# MTRduino_Rev3_1.net
KiCad netlist of a schematic drawn in EAGLE
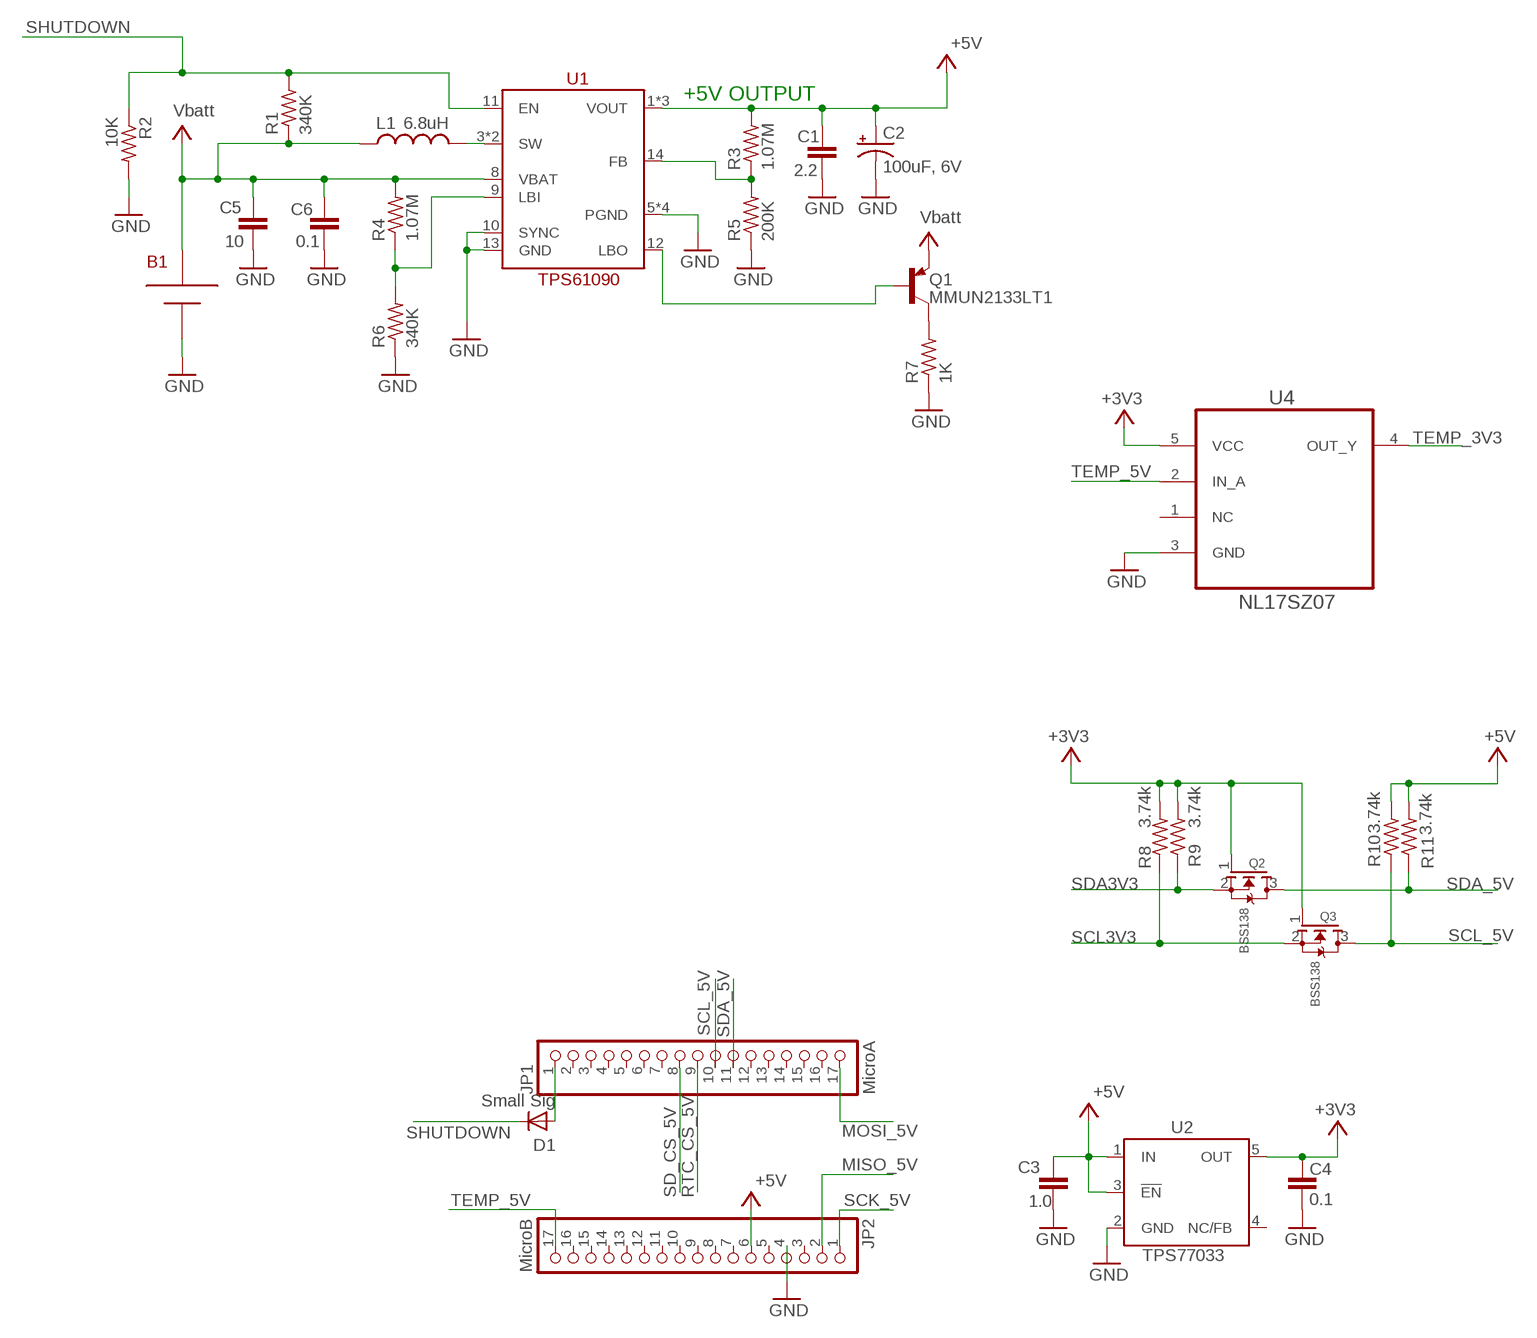
[diagram p0: schematic, sheet 1, part 1 of 2]
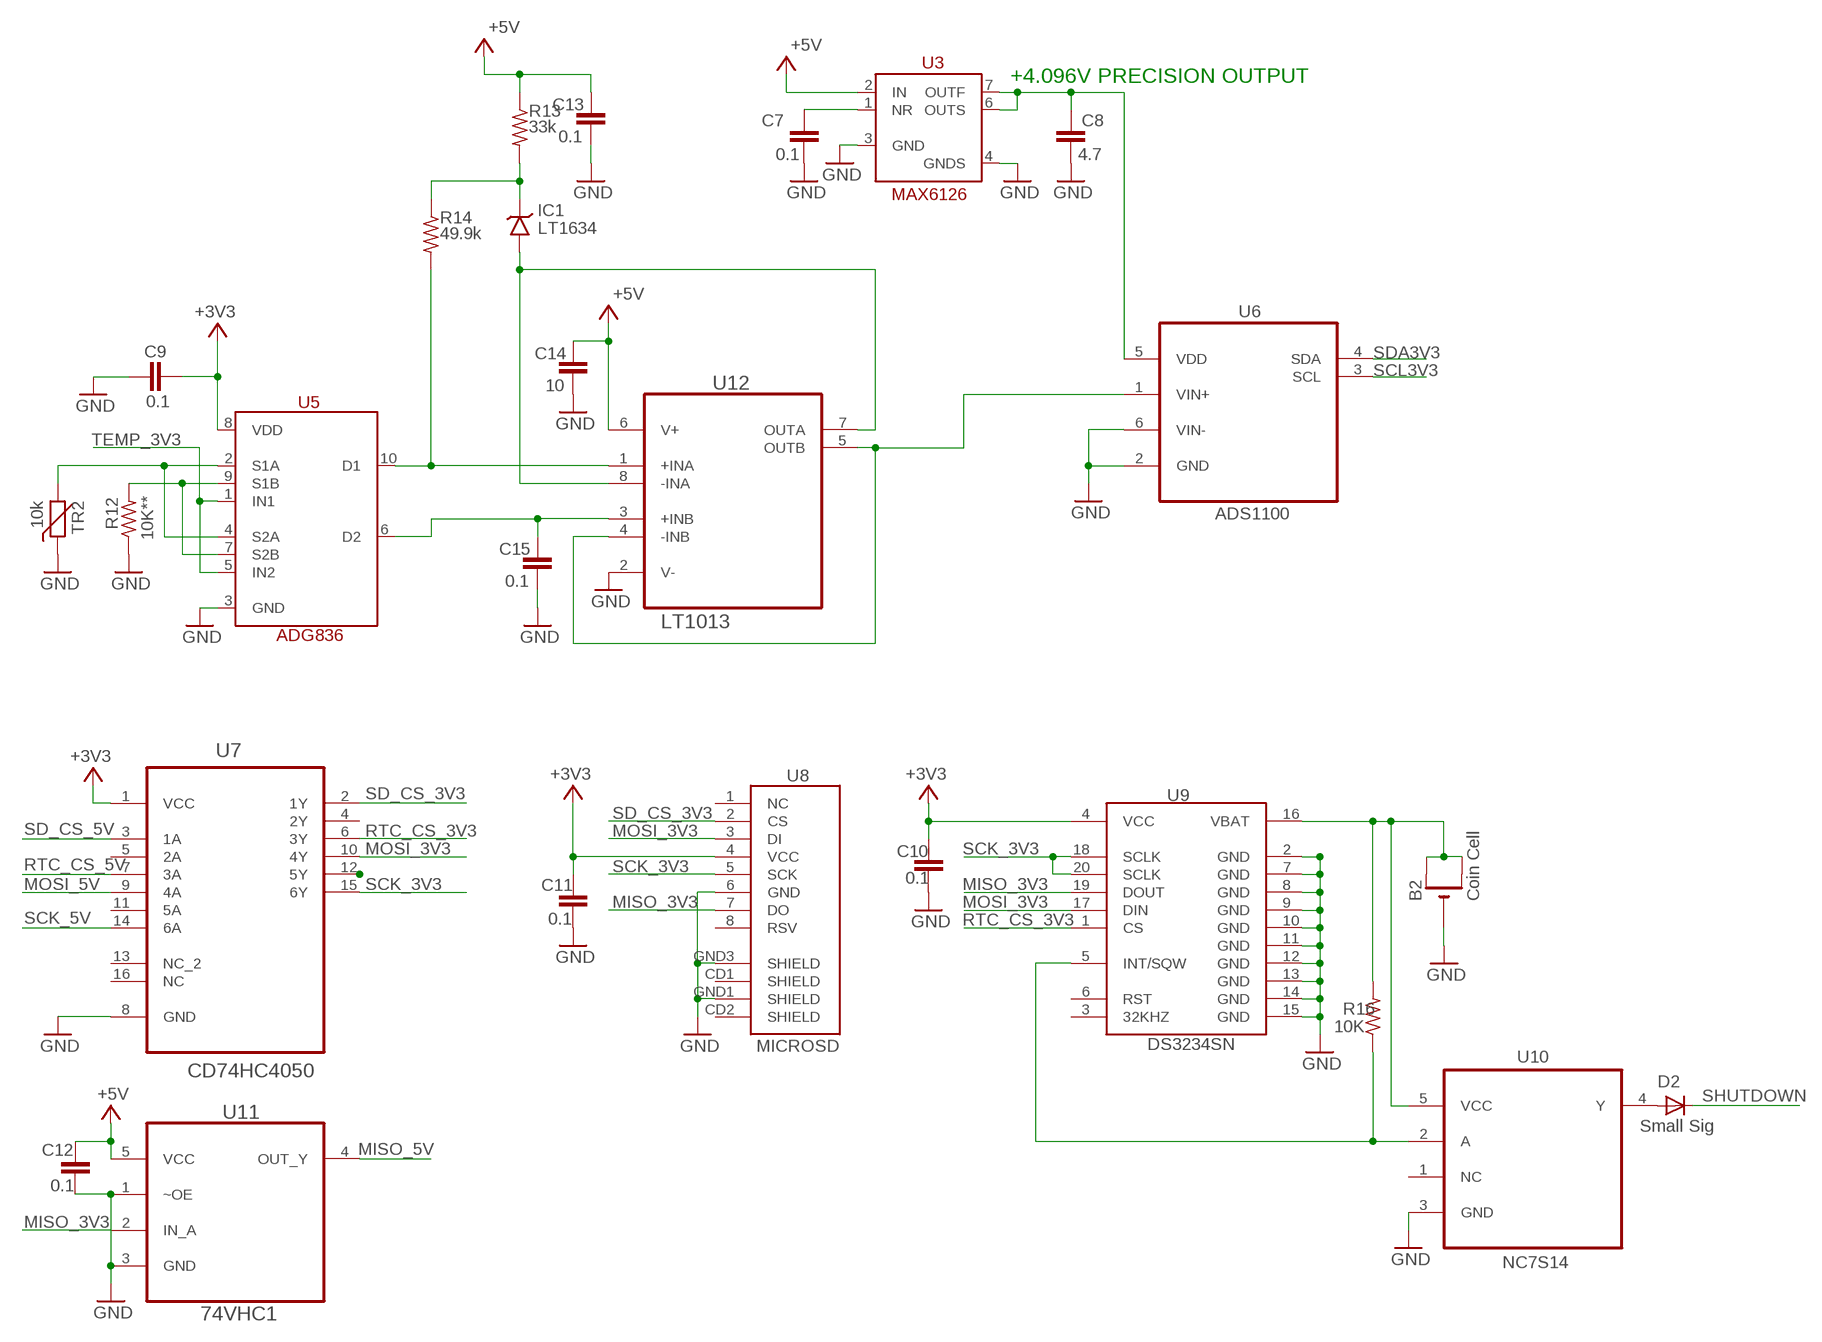
[diagram p1: schematic, sheet 1, part 2 of 2]

(export (version "E")
  (design (tool "Eeschema 10.0.6"))
  (components
    (comp (ref "B1")
      (value "2x AA BATT")
      (footprint "eagle-import:BATT_AA2")
      (libsource (lib "eagle-import") (part "BATT_AA2"))
    )
    (comp (ref "B2")
      (value "Coin Cell")
      (footprint "eagle-import:CR1220-SMD")
      (libsource (lib "eagle-import") (part "CR1220SMT"))
    )
    (comp (ref "C1")
      (value "2.2")
      (footprint "eagle-import:C0603")
      (libsource (lib "eagle-import") (part "C-EUC0603"))
    )
    (comp (ref "C2")
      (value "100uF, 6V")
      (footprint "eagle-import:A_3216-18R")
      (libsource (lib "eagle-import") (part "CPOL-USA/3216-18R"))
    )
    (comp (ref "C3")
      (value "1.0")
      (footprint "eagle-import:C0603")
      (libsource (lib "eagle-import") (part "C-EUC0603"))
    )
    (comp (ref "C4")
      (value "0.1")
      (footprint "eagle-import:C0603")
      (libsource (lib "eagle-import") (part "C-EUC0603"))
    )
    (comp (ref "C5")
      (value "10")
      (footprint "eagle-import:C0603")
      (libsource (lib "eagle-import") (part "C-EUC0603"))
    )
    (comp (ref "C6")
      (value "0.1")
      (footprint "eagle-import:C0603")
      (libsource (lib "eagle-import") (part "C-EUC0603"))
    )
    (comp (ref "C7")
      (value "0.1")
      (footprint "eagle-import:C0603")
      (libsource (lib "eagle-import") (part "C-EUC0603"))
    )
    (comp (ref "C8")
      (value "4.7")
      (footprint "eagle-import:C0603")
      (libsource (lib "eagle-import") (part "C-EUC0603"))
    )
    (comp (ref "C9")
      (value "0.1")
      (footprint "eagle-import:C0603")
      (libsource (lib "eagle-import") (part "C-EUC0603"))
    )
    (comp (ref "C10")
      (value "0.1")
      (footprint "eagle-import:C0603")
      (libsource (lib "eagle-import") (part "C-EUC0603"))
    )
    (comp (ref "C11")
      (value "0.1")
      (footprint "eagle-import:C0603")
      (libsource (lib "eagle-import") (part "C-EUC0603"))
    )
    (comp (ref "C12")
      (value "0.1")
      (footprint "eagle-import:C0603")
      (libsource (lib "eagle-import") (part "C-EUC0603"))
    )
    (comp (ref "C13")
      (value "0.1")
      (footprint "eagle-import:C0603")
      (libsource (lib "eagle-import") (part "C-EUC0603"))
    )
    (comp (ref "C14")
      (value "10")
      (footprint "eagle-import:C0603")
      (libsource (lib "eagle-import") (part "C-EUC0603"))
    )
    (comp (ref "C15")
      (value "0.1")
      (footprint "eagle-import:C0603")
      (libsource (lib "eagle-import") (part "C-EUC0603"))
    )
    (comp (ref "D1")
      (value "Small Sig")
      (footprint "eagle-import:SOD-323F")
      (libsource (lib "eagle-import") (part "DIODESOD-323F"))
    )
    (comp (ref "D2")
      (value "Small Sig")
      (footprint "eagle-import:SOD-323F")
      (libsource (lib "eagle-import") (part "DIODESOD-323F"))
    )
    (comp (ref "IC1")
      (value "LT1634")
      (footprint "eagle-import:S8")
      (libsource (lib "eagle-import") (part "LT1634BIS8-1.25"))
    )
    (comp (ref "JP1")
      (value "MicroA")
      (footprint "eagle-import:1X17")
      (libsource (lib "eagle-import") (part "PINHD-1X17"))
    )
    (comp (ref "JP2")
      (value "MicroB")
      (footprint "eagle-import:1X17")
      (libsource (lib "eagle-import") (part "PINHD-1X17"))
    )
    (comp (ref "L1")
      (value "6.8uH")
      (footprint "eagle-import:L2012C")
      (libsource (lib "eagle-import") (part "L-USL2012C"))
    )
    (comp (ref "Q1")
      (value "MMUN2133LT1")
      (footprint "eagle-import:SC59-BEC")
      (libsource (lib "eagle-import") (part "MMUN2111LT1"))
    )
    (comp (ref "Q2")
      (value "BSS138")
      (footprint "eagle-import:SOT23")
      (libsource (lib "eagle-import") (part "MOSFET-NREFLOW"))
    )
    (comp (ref "Q3")
      (value "BSS138")
      (footprint "eagle-import:SOT23")
      (libsource (lib "eagle-import") (part "MOSFET-NREFLOW"))
    )
    (comp (ref "R1")
      (value "340K")
      (footprint "eagle-import:R0603")
      (libsource (lib "eagle-import") (part "resistor_R-US_R0603"))
    )
    (comp (ref "R2")
      (value "10K")
      (footprint "eagle-import:R0603")
      (libsource (lib "eagle-import") (part "resistor_R-US_R0603"))
    )
    (comp (ref "R3")
      (value "1.07M")
      (footprint "eagle-import:R0603")
      (libsource (lib "eagle-import") (part "resistor_R-US_R0603"))
    )
    (comp (ref "R4")
      (value "1.07M")
      (footprint "eagle-import:R0603")
      (libsource (lib "eagle-import") (part "resistor_R-US_R0603"))
    )
    (comp (ref "R5")
      (value "200K")
      (footprint "eagle-import:R0603")
      (libsource (lib "eagle-import") (part "resistor_R-US_R0603"))
    )
    (comp (ref "R6")
      (value "340K")
      (footprint "eagle-import:R0603")
      (libsource (lib "eagle-import") (part "resistor_R-US_R0603"))
    )
    (comp (ref "R7")
      (value "1K")
      (footprint "eagle-import:R0603")
      (libsource (lib "eagle-import") (part "resistor_R-US_R0603"))
    )
    (comp (ref "R8")
      (value "3.74k")
      (footprint "eagle-import:R0603")
      (libsource (lib "eagle-import") (part "resistor_R-US_R0603"))
    )
    (comp (ref "R9")
      (value "3.74k")
      (footprint "eagle-import:R0603")
      (libsource (lib "eagle-import") (part "resistor_R-US_R0603"))
    )
    (comp (ref "R10")
      (value "3.74k")
      (footprint "eagle-import:R0603")
      (libsource (lib "eagle-import") (part "resistor_R-US_R0603"))
    )
    (comp (ref "R11")
      (value "3.74k")
      (footprint "eagle-import:R0603")
      (libsource (lib "eagle-import") (part "resistor_R-US_R0603"))
    )
    (comp (ref "R12")
      (value "10K**")
      (footprint "eagle-import:R1206")
      (libsource (lib "eagle-import") (part "R-US_R1206"))
    )
    (comp (ref "R13")
      (value "33k")
      (footprint "eagle-import:R0603")
      (libsource (lib "eagle-import") (part "resistor_R-US_R0603"))
    )
    (comp (ref "R14")
      (value "49.9k")
      (footprint "eagle-import:R0603")
      (libsource (lib "eagle-import") (part "resistor_R-US_R0603"))
    )
    (comp (ref "R16")
      (value "10K")
      (footprint "eagle-import:R0603")
      (libsource (lib "eagle-import") (part "resistor_R-US_R0603"))
    )
    (comp (ref "TR2")
      (value "10k")
      (footprint "eagle-import:R-5")
      (libsource (lib "eagle-import") (part "THERMISTOR_R-5"))
    )
    (comp (ref "U1")
      (value "TPS61090")
      (footprint "eagle-import:QFN16-4X4")
      (libsource (lib "eagle-import") (part "TPS61090RSAR"))
    )
    (comp (ref "U2")
      (value "TPS77033")
      (footprint "eagle-import:SOT23-DBV")
      (fields (field (name "MF") "TEXAS INSTRUMENTS") (field (name "MPN") "TPS77030DBVT"))
      (libsource (lib "eagle-import") (part "TPS77030"))
    )
    (comp (ref "U3")
      (value "MAX6126")
      (footprint "eagle-import:SOIC127P600X175-8N")
      (libsource (lib "eagle-import") (part "MAX6126"))
    )
    (comp (ref "U4")
      (value "NL17SZ07")
      (footprint "eagle-import:SOT65P210X110-5N")
      (fields (field (name "MPN") "NL17SZ07DFT2G"))
      (libsource (lib "eagle-import") (part "NL17SZ07DFT2G"))
    )
    (comp (ref "U5")
      (value "ADG836")
      (footprint "eagle-import:MSOP10")
      (libsource (lib "eagle-import") (part "ADG836"))
    )
    (comp (ref "U6")
      (value "ADS1100")
      (footprint "eagle-import:SOT95P280X145-6N")
      (fields (field (name "MPN") "ADS1100A0IDBVT"))
      (libsource (lib "eagle-import") (part "ADS1100A0IDBVT"))
    )
    (comp (ref "U7")
      (value "CD74HC4050")
      (footprint "eagle-import:SOIC127P600X175-16N")
      (fields (field (name "MPN") "M74HC4050RM13TR"))
      (libsource (lib "eagle-import") (part "M74HC4050RM13TR"))
    )
    (comp (ref "U8")
      (value "MICROSD")
      (footprint "eagle-import:MICRO-SD-SOCKET-PP")
      (libsource (lib "eagle-import") (part "USD-SOCKETNEW"))
    )
    (comp (ref "U9")
      (value "DS3234SN")
      (footprint "eagle-import:DS3234")
      (libsource (lib "eagle-import") (part "DS3234"))
    )
    (comp (ref "U10")
      (value "NC7S14")
      (footprint "eagle-import:SOT95P280X145-5N")
      (fields (field (name "MPN") "1P1G14MDBVREPG4"))
      (libsource (lib "eagle-import") (part "1P1G14MDBVREPG4"))
    )
    (comp (ref "U11")
      (value "74VHC1")
      (footprint "eagle-import:SOT65P210X110-5N")
      (fields (field (name "MPN") "M74VHC1GT125DF1G"))
      (libsource (lib "eagle-import") (part "M74VHC1GT125DF1G"))
    )
    (comp (ref "U12")
      (value "LT1013")
      (footprint "eagle-import:SOIC127P600X175-8N")
      (fields (field (name "MPN") "LT1013DS8#PBF"))
      (libsource (lib "eagle-import") (part "LT1013DS8PBF"))
    )
  )
  (nets
    (net (code "1") (name "+3V3") (class "Default")
      (node (ref "C10") (pin "1") (pinfunction "1_1") (pintype "passive"))
      (node (ref "C11") (pin "1") (pinfunction "1_1") (pintype "passive"))
      (node (ref "C4") (pin "1") (pinfunction "1_1") (pintype "passive"))
      (node (ref "C9") (pin "2") (pinfunction "2_2") (pintype "passive"))
      (node (ref "Q2") (pin "1") (pinfunction "G_1") (pintype "bidirectional"))
      (node (ref "Q3") (pin "1") (pinfunction "G_1") (pintype "bidirectional"))
      (node (ref "R8") (pin "2") (pinfunction "2_2") (pintype "passive"))
      (node (ref "R9") (pin "2") (pinfunction "2_2") (pintype "passive"))
      (node (ref "U2") (pin "5") (pinfunction "OUT_5") (pintype "passive"))
      (node (ref "U4") (pin "5") (pinfunction "VCC_5") (pintype "power_in"))
      (node (ref "U5") (pin "8") (pinfunction "VDD_8") (pintype "bidirectional"))
      (node (ref "U7") (pin "1") (pinfunction "VCC_1") (pintype "power_in"))
      (node (ref "U8") (pin "4") (pinfunction "VCC_4") (pintype "bidirectional"))
      (node (ref "U9") (pin "4") (pinfunction "VCC_4") (pintype "bidirectional"))
    )
    (net (code "2") (name "+5V") (class "Default")
      (node (ref "C1") (pin "1") (pinfunction "1_1") (pintype "passive"))
      (node (ref "C12") (pin "1") (pinfunction "1_1") (pintype "passive"))
      (node (ref "C13") (pin "2") (pinfunction "2_2") (pintype "passive"))
      (node (ref "C14") (pin "2") (pinfunction "2_2") (pintype "passive"))
      (node (ref "C2") (pin "+") (pinfunction "+_+") (pintype "passive"))
      (node (ref "C3") (pin "1") (pinfunction "1_1") (pintype "passive"))
      (node (ref "JP2") (pin "6") (pinfunction "6_6") (pintype "passive"))
      (node (ref "R10") (pin "2") (pinfunction "2_2") (pintype "passive"))
      (node (ref "R11") (pin "2") (pinfunction "2_2") (pintype "passive"))
      (node (ref "R13") (pin "1") (pinfunction "1_1") (pintype "passive"))
      (node (ref "R3") (pin "2") (pinfunction "2_2") (pintype "passive"))
      (node (ref "U1") (pin "1") (pinfunction "VOUT_1") (pintype "bidirectional"))
      (node (ref "U1") (pin "15") (pinfunction "VOUT_15") (pintype "bidirectional"))
      (node (ref "U1") (pin "16") (pinfunction "VOUT_16") (pintype "bidirectional"))
      (node (ref "U11") (pin "5") (pinfunction "VCC_5") (pintype "power_in"))
      (node (ref "U12") (pin "6") (pinfunction "V+_6") (pintype "power_in"))
      (node (ref "U2") (pin "1") (pinfunction "IN_1") (pintype "input"))
      (node (ref "U2") (pin "3") (pinfunction "~{EN}_3") (pintype "input"))
      (node (ref "U3") (pin "2") (pinfunction "IN_2") (pintype "input"))
    )
    (net (code "3") (name "/MISO_3V3") (class "Default")
      (node (ref "U11") (pin "2") (pinfunction "IN_A_2") (pintype "input"))
      (node (ref "U8") (pin "7") (pinfunction "DO_7") (pintype "bidirectional"))
      (node (ref "U9") (pin "19") (pinfunction "DOUT_19") (pintype "bidirectional"))
    )
    (net (code "4") (name "/MISO_5V") (class "Default")
      (node (ref "JP2") (pin "2") (pinfunction "2_2") (pintype "passive"))
      (node (ref "U11") (pin "4") (pinfunction "OUT_Y_4") (pintype "output"))
    )
    (net (code "5") (name "/MOSI_3V3") (class "Default")
      (node (ref "U7") (pin "10") (pinfunction "4Y_10") (pintype "output"))
      (node (ref "U8") (pin "3") (pinfunction "DI_3") (pintype "bidirectional"))
      (node (ref "U9") (pin "17") (pinfunction "DIN_17") (pintype "bidirectional"))
    )
    (net (code "6") (name "/MOSI_5V") (class "Default")
      (node (ref "JP1") (pin "17") (pinfunction "17_17") (pintype "passive"))
      (node (ref "U7") (pin "9") (pinfunction "4A_9") (pintype "input"))
    )
    (net (code "7") (name "/RTC_CS_3V3") (class "Default")
      (node (ref "U7") (pin "6") (pinfunction "3Y_6") (pintype "output"))
      (node (ref "U9") (pin "1") (pinfunction "CS_1") (pintype "bidirectional"))
    )
    (net (code "8") (name "/RTC_CS_5V") (class "Default")
      (node (ref "JP1") (pin "9") (pinfunction "9_9") (pintype "passive"))
      (node (ref "U7") (pin "7") (pinfunction "3A_7") (pintype "input"))
    )
    (net (code "9") (name "/SCK_3V3") (class "Default")
      (node (ref "U7") (pin "15") (pinfunction "6Y_15") (pintype "output"))
      (node (ref "U8") (pin "5") (pinfunction "SCK_5") (pintype "bidirectional"))
      (node (ref "U9") (pin "18") (pinfunction "SCLK_18") (pintype "bidirectional"))
      (node (ref "U9") (pin "20") (pinfunction "SCLK_20") (pintype "bidirectional"))
    )
    (net (code "10") (name "/SCK_5V") (class "Default")
      (node (ref "JP2") (pin "1") (pinfunction "1_1") (pintype "passive"))
      (node (ref "U7") (pin "14") (pinfunction "6A_14") (pintype "input"))
    )
    (net (code "11") (name "/SCL3V3") (class "Default")
      (node (ref "Q3") (pin "2") (pinfunction "S_2") (pintype "bidirectional"))
      (node (ref "R8") (pin "1") (pinfunction "1_1") (pintype "passive"))
      (node (ref "U6") (pin "3") (pinfunction "SCL_3") (pintype "output"))
    )
    (net (code "12") (name "/SCL_5V") (class "Default")
      (node (ref "JP1") (pin "10") (pinfunction "10_10") (pintype "passive"))
      (node (ref "Q3") (pin "3") (pinfunction "D_3") (pintype "bidirectional"))
      (node (ref "R10") (pin "1") (pinfunction "1_1") (pintype "passive"))
    )
    (net (code "13") (name "/SDA3V3") (class "Default")
      (node (ref "Q2") (pin "2") (pinfunction "S_2") (pintype "bidirectional"))
      (node (ref "R9") (pin "1") (pinfunction "1_1") (pintype "passive"))
      (node (ref "U6") (pin "4") (pinfunction "SDA_4") (pintype "output"))
    )
    (net (code "14") (name "/SDA_5V") (class "Default")
      (node (ref "JP1") (pin "11") (pinfunction "11_11") (pintype "passive"))
      (node (ref "Q2") (pin "3") (pinfunction "D_3") (pintype "bidirectional"))
      (node (ref "R11") (pin "1") (pinfunction "1_1") (pintype "passive"))
    )
    (net (code "15") (name "/SD_CS_3V3") (class "Default")
      (node (ref "U7") (pin "2") (pinfunction "1Y_2") (pintype "output"))
      (node (ref "U8") (pin "2") (pinfunction "CS_2") (pintype "bidirectional"))
    )
    (net (code "16") (name "/SD_CS_5V") (class "Default")
      (node (ref "JP1") (pin "8") (pinfunction "8_8") (pintype "passive"))
      (node (ref "U7") (pin "3") (pinfunction "1A_3") (pintype "input"))
    )
    (net (code "17") (name "/SHUTDOWN") (class "Default")
      (node (ref "D1") (pin "C") (pinfunction "C_C") (pintype "passive"))
      (node (ref "D2") (pin "C") (pinfunction "C_C") (pintype "passive"))
      (node (ref "R1") (pin "2") (pinfunction "2_2") (pintype "passive"))
      (node (ref "R2") (pin "1") (pinfunction "1_1") (pintype "passive"))
      (node (ref "U1") (pin "11") (pinfunction "EN_11") (pintype "bidirectional"))
    )
    (net (code "18") (name "/TEMP_3V3") (class "Default")
      (node (ref "U4") (pin "4") (pinfunction "OUT_Y_4") (pintype "output"))
      (node (ref "U5") (pin "1") (pinfunction "IN1_1") (pintype "bidirectional"))
      (node (ref "U5") (pin "5") (pinfunction "IN2_5") (pintype "bidirectional"))
    )
    (net (code "19") (name "/TEMP_5V") (class "Default")
      (node (ref "JP2") (pin "17") (pinfunction "17_17") (pintype "passive"))
      (node (ref "U4") (pin "2") (pinfunction "IN_A_2") (pintype "input"))
    )
    (net (code "20") (name "GND") (class "Default")
      (node (ref "B1") (pin "+") (pinfunction "+_+") (pintype "bidirectional"))
      (node (ref "B2") (pin "-") (pinfunction "-_-") (pintype "passive"))
      (node (ref "C1") (pin "2") (pinfunction "2_2") (pintype "passive"))
      (node (ref "C10") (pin "2") (pinfunction "2_2") (pintype "passive"))
      (node (ref "C11") (pin "2") (pinfunction "2_2") (pintype "passive"))
      (node (ref "C12") (pin "2") (pinfunction "2_2") (pintype "passive"))
      (node (ref "C13") (pin "1") (pinfunction "1_1") (pintype "passive"))
      (node (ref "C14") (pin "1") (pinfunction "1_1") (pintype "passive"))
      (node (ref "C15") (pin "1") (pinfunction "1_1") (pintype "passive"))
      (node (ref "C2") (pin "-") (pinfunction "-_-") (pintype "passive"))
      (node (ref "C3") (pin "2") (pinfunction "2_2") (pintype "passive"))
      (node (ref "C4") (pin "2") (pinfunction "2_2") (pintype "passive"))
      (node (ref "C5") (pin "2") (pinfunction "2_2") (pintype "passive"))
      (node (ref "C6") (pin "2") (pinfunction "2_2") (pintype "passive"))
      (node (ref "C7") (pin "2") (pinfunction "2_2") (pintype "passive"))
      (node (ref "C8") (pin "2") (pinfunction "2_2") (pintype "passive"))
      (node (ref "C9") (pin "1") (pinfunction "1_1") (pintype "passive"))
      (node (ref "JP2") (pin "4") (pinfunction "4_4") (pintype "passive"))
      (node (ref "R12") (pin "1") (pinfunction "1_1") (pintype "passive"))
      (node (ref "R2") (pin "2") (pinfunction "2_2") (pintype "passive"))
      (node (ref "R5") (pin "1") (pinfunction "1_1") (pintype "passive"))
      (node (ref "R6") (pin "1") (pinfunction "1_1") (pintype "passive"))
      (node (ref "R7") (pin "1") (pinfunction "1_1") (pintype "passive"))
      (node (ref "TR2") (pin "1") (pinfunction "1_1") (pintype "passive"))
      (node (ref "U1") (pin "10") (pinfunction "SYNC_10") (pintype "bidirectional"))
      (node (ref "U1") (pin "13") (pinfunction "GND_13") (pintype "bidirectional"))
      (node (ref "U1") (pin "5") (pinfunction "PGND_5") (pintype "bidirectional"))
      (node (ref "U1") (pin "6") (pinfunction "PGND_6") (pintype "bidirectional"))
      (node (ref "U1") (pin "7") (pinfunction "PGND_7") (pintype "bidirectional"))
      (node (ref "U1") (pin "EXP") (pinfunction "PGND_EXP") (pintype "bidirectional"))
      (node (ref "U10") (pin "3") (pinfunction "GND_3") (pintype "passive"))
      (node (ref "U11") (pin "1") (pinfunction "~{OE}_1") (pintype "input"))
      (node (ref "U11") (pin "3") (pinfunction "GND_3") (pintype "passive"))
      (node (ref "U12") (pin "2") (pinfunction "V-_2") (pintype "power_in"))
      (node (ref "U2") (pin "2") (pinfunction "GND_2") (pintype "power_in"))
      (node (ref "U3") (pin "3") (pinfunction "GND_3") (pintype "input"))
      (node (ref "U3") (pin "4") (pinfunction "GNDS_4") (pintype "input"))
      (node (ref "U4") (pin "3") (pinfunction "GND_3") (pintype "passive"))
      (node (ref "U5") (pin "3") (pinfunction "GND_3") (pintype "bidirectional"))
      (node (ref "U6") (pin "2") (pinfunction "GND_2") (pintype "passive"))
      (node (ref "U6") (pin "6") (pinfunction "VIN-_6") (pintype "input"))
      (node (ref "U7") (pin "8") (pinfunction "GND_8") (pintype "passive"))
      (node (ref "U8") (pin "6") (pinfunction "GND_6") (pintype "bidirectional"))
      (node (ref "U8") (pin "GND1") (pinfunction "SHIELD_GND1") (pintype "bidirectional"))
      (node (ref "U8") (pin "GND3") (pinfunction "SHIELD_GND3") (pintype "bidirectional"))
      (node (ref "U9") (pin "10") (pinfunction "GND_10") (pintype "bidirectional"))
      (node (ref "U9") (pin "11") (pinfunction "GND_11") (pintype "bidirectional"))
      (node (ref "U9") (pin "12") (pinfunction "GND_12") (pintype "bidirectional"))
      (node (ref "U9") (pin "13") (pinfunction "GND_13") (pintype "bidirectional"))
      (node (ref "U9") (pin "14") (pinfunction "GND_14") (pintype "bidirectional"))
      (node (ref "U9") (pin "15") (pinfunction "GND_15") (pintype "bidirectional"))
      (node (ref "U9") (pin "2") (pinfunction "GND_2") (pintype "bidirectional"))
      (node (ref "U9") (pin "7") (pinfunction "GND_7") (pintype "bidirectional"))
      (node (ref "U9") (pin "8") (pinfunction "GND_8") (pintype "bidirectional"))
      (node (ref "U9") (pin "9") (pinfunction "GND_9") (pintype "bidirectional"))
    )
    (net (code "21") (name "Net-(B2-+)") (class "Default")
      (node (ref "B2") (pin "+$1") (pinfunction "+_+$1") (pintype "passive"))
      (node (ref "B2") (pin "+$2") (pinfunction "+1_+$2") (pintype "passive"))
      (node (ref "R16") (pin "2") (pinfunction "2_2") (pintype "passive"))
      (node (ref "U10") (pin "5") (pinfunction "VCC_5") (pintype "power_in"))
      (node (ref "U9") (pin "16") (pinfunction "VBAT_16") (pintype "bidirectional"))
    )
    (net (code "22") (name "Net-(D1-PadA)") (class "Default")
      (node (ref "D1") (pin "A") (pinfunction "A_A") (pintype "passive"))
      (node (ref "JP1") (pin "1") (pinfunction "1_1") (pintype "passive"))
    )
    (net (code "23") (name "Net-(IC1-GND)") (class "Default")
      (node (ref "IC1") (pin "4") (pinfunction "GND_4") (pintype "passive"))
      (node (ref "U12") (pin "7") (pinfunction "OUTA_7") (pintype "output"))
      (node (ref "U12") (pin "8") (pinfunction "-INA_8") (pintype "input"))
    )
    (net (code "24") (name "Net-(IC1-VOUT)") (class "Default")
      (node (ref "IC1") (pin "6") (pinfunction "VOUT_6") (pintype "passive"))
      (node (ref "R13") (pin "2") (pinfunction "2_2") (pintype "passive"))
      (node (ref "R14") (pin "1") (pinfunction "1_1") (pintype "passive"))
    )
    (net (code "25") (name "Net-(L1-Pad2)") (class "Default")
      (node (ref "L1") (pin "2") (pinfunction "2_2") (pintype "passive"))
      (node (ref "U1") (pin "3") (pinfunction "SW_3") (pintype "bidirectional"))
      (node (ref "U1") (pin "4") (pinfunction "SW_4") (pintype "bidirectional"))
    )
    (net (code "26") (name "Net-(Q1-PadC)") (class "Default")
      (node (ref "Q1") (pin "C") (pinfunction "C_C") (pintype "passive"))
      (node (ref "R7") (pin "2") (pinfunction "2_2") (pintype "passive"))
    )
    (net (code "27") (name "Net-(U1-FB)") (class "Default")
      (node (ref "R3") (pin "1") (pinfunction "1_1") (pintype "passive"))
      (node (ref "R5") (pin "2") (pinfunction "2_2") (pintype "passive"))
      (node (ref "U1") (pin "14") (pinfunction "FB_14") (pintype "bidirectional"))
    )
    (net (code "28") (name "Net-(U1-LBI)") (class "Default")
      (node (ref "R4") (pin "1") (pinfunction "1_1") (pintype "passive"))
      (node (ref "R6") (pin "2") (pinfunction "2_2") (pintype "passive"))
      (node (ref "U1") (pin "9") (pinfunction "LBI_9") (pintype "bidirectional"))
    )
    (net (code "29") (name "Net-(U1-LBO)") (class "Default")
      (node (ref "Q1") (pin "B") (pinfunction "B_B") (pintype "passive"))
      (node (ref "U1") (pin "12") (pinfunction "LBO_12") (pintype "bidirectional"))
    )
    (net (code "30") (name "Net-(U3-NR)") (class "Default")
      (node (ref "C7") (pin "1") (pinfunction "1_1") (pintype "passive"))
      (node (ref "U3") (pin "1") (pinfunction "NR_1") (pintype "bidirectional"))
    )
    (net (code "31") (name "Net-(U3-OUTF)") (class "Default")
      (node (ref "C8") (pin "1") (pinfunction "1_1") (pintype "passive"))
      (node (ref "U3") (pin "6") (pinfunction "OUTS_6") (pintype "output"))
      (node (ref "U3") (pin "7") (pinfunction "OUTF_7") (pintype "output"))
      (node (ref "U6") (pin "5") (pinfunction "VDD_5") (pintype "power_in"))
    )
    (net (code "32") (name "Net-(U5-S1A)") (class "Default")
      (node (ref "TR2") (pin "2") (pinfunction "2_2") (pintype "passive"))
      (node (ref "U5") (pin "2") (pinfunction "S1A_2") (pintype "bidirectional"))
      (node (ref "U5") (pin "4") (pinfunction "S2A_4") (pintype "bidirectional"))
    )
    (net (code "33") (name "Net-(U5-S1B)") (class "Default")
      (node (ref "R12") (pin "2") (pinfunction "2_2") (pintype "passive"))
      (node (ref "U5") (pin "7") (pinfunction "S2B_7") (pintype "bidirectional"))
      (node (ref "U5") (pin "9") (pinfunction "S1B_9") (pintype "bidirectional"))
    )
    (net (code "34") (name "Net-(U10-A)") (class "Default")
      (node (ref "R16") (pin "1") (pinfunction "1_1") (pintype "passive"))
      (node (ref "U10") (pin "2") (pinfunction "A_2") (pintype "input"))
      (node (ref "U9") (pin "5") (pinfunction "INT/SQW_5") (pintype "bidirectional"))
    )
    (net (code "35") (name "Net-(U10-Y)") (class "Default")
      (node (ref "D2") (pin "A") (pinfunction "A_A") (pintype "passive"))
      (node (ref "U10") (pin "4") (pinfunction "Y_4") (pintype "output"))
    )
    (net (code "36") (name "Net-(U12-+INA)") (class "Default")
      (node (ref "R14") (pin "2") (pinfunction "2_2") (pintype "passive"))
      (node (ref "U12") (pin "1") (pinfunction "+INA_1") (pintype "input"))
      (node (ref "U5") (pin "10") (pinfunction "D1_10") (pintype "bidirectional"))
    )
    (net (code "37") (name "Net-(U12-+INB)") (class "Default")
      (node (ref "C15") (pin "2") (pinfunction "2_2") (pintype "passive"))
      (node (ref "U12") (pin "3") (pinfunction "+INB_3") (pintype "input"))
      (node (ref "U5") (pin "6") (pinfunction "D2_6") (pintype "bidirectional"))
    )
    (net (code "38") (name "Net-(U12--INB)") (class "Default")
      (node (ref "U12") (pin "4") (pinfunction "-INB_4") (pintype "input"))
      (node (ref "U12") (pin "5") (pinfunction "OUTB_5") (pintype "output"))
      (node (ref "U6") (pin "1") (pinfunction "VIN+_1") (pintype "input"))
    )
    (net (code "39") (name "Vbatt") (class "Default")
      (node (ref "B1") (pin "-") (pinfunction "-_-") (pintype "bidirectional"))
      (node (ref "C5") (pin "1") (pinfunction "1_1") (pintype "passive"))
      (node (ref "C6") (pin "1") (pinfunction "1_1") (pintype "passive"))
      (node (ref "L1") (pin "1") (pinfunction "1_1") (pintype "passive"))
      (node (ref "Q1") (pin "E") (pinfunction "E_E") (pintype "passive"))
      (node (ref "R1") (pin "1") (pinfunction "1_1") (pintype "passive"))
      (node (ref "R4") (pin "2") (pinfunction "2_2") (pintype "passive"))
      (node (ref "U1") (pin "8") (pinfunction "VBAT_8") (pintype "bidirectional"))
    )
    (net (code "40") (name "unconnected-(JP1-Pad2)") (class "Default")
      (node (ref "JP1") (pin "2") (pinfunction "2_2") (pintype "passive"))
    )
    (net (code "41") (name "unconnected-(JP1-Pad3)") (class "Default")
      (node (ref "JP1") (pin "3") (pinfunction "3_3") (pintype "passive"))
    )
    (net (code "42") (name "unconnected-(JP1-Pad4)") (class "Default")
      (node (ref "JP1") (pin "4") (pinfunction "4_4") (pintype "passive"))
    )
    (net (code "43") (name "unconnected-(JP1-Pad5)") (class "Default")
      (node (ref "JP1") (pin "5") (pinfunction "5_5") (pintype "passive"))
    )
    (net (code "44") (name "unconnected-(JP1-Pad6)") (class "Default")
      (node (ref "JP1") (pin "6") (pinfunction "6_6") (pintype "passive"))
    )
    (net (code "45") (name "unconnected-(JP1-Pad7)") (class "Default")
      (node (ref "JP1") (pin "7") (pinfunction "7_7") (pintype "passive"))
    )
    (net (code "46") (name "unconnected-(JP1-Pad12)") (class "Default")
      (node (ref "JP1") (pin "12") (pinfunction "12_12") (pintype "passive"))
    )
    (net (code "47") (name "unconnected-(JP1-Pad13)") (class "Default")
      (node (ref "JP1") (pin "13") (pinfunction "13_13") (pintype "passive"))
    )
    (net (code "48") (name "unconnected-(JP1-Pad14)") (class "Default")
      (node (ref "JP1") (pin "14") (pinfunction "14_14") (pintype "passive"))
    )
    (net (code "49") (name "unconnected-(JP1-Pad15)") (class "Default")
      (node (ref "JP1") (pin "15") (pinfunction "15_15") (pintype "passive"))
    )
    (net (code "50") (name "unconnected-(JP1-Pad16)") (class "Default")
      (node (ref "JP1") (pin "16") (pinfunction "16_16") (pintype "passive"))
    )
    (net (code "51") (name "unconnected-(JP2-Pad3)") (class "Default")
      (node (ref "JP2") (pin "3") (pinfunction "3_3") (pintype "passive"))
    )
    (net (code "52") (name "unconnected-(JP2-Pad5)") (class "Default")
      (node (ref "JP2") (pin "5") (pinfunction "5_5") (pintype "passive"))
    )
    (net (code "53") (name "unconnected-(JP2-Pad7)") (class "Default")
      (node (ref "JP2") (pin "7") (pinfunction "7_7") (pintype "passive"))
    )
    (net (code "54") (name "unconnected-(JP2-Pad8)") (class "Default")
      (node (ref "JP2") (pin "8") (pinfunction "8_8") (pintype "passive"))
    )
    (net (code "55") (name "unconnected-(JP2-Pad9)") (class "Default")
      (node (ref "JP2") (pin "9") (pinfunction "9_9") (pintype "passive"))
    )
    (net (code "56") (name "unconnected-(JP2-Pad10)") (class "Default")
      (node (ref "JP2") (pin "10") (pinfunction "10_10") (pintype "passive"))
    )
    (net (code "57") (name "unconnected-(JP2-Pad11)") (class "Default")
      (node (ref "JP2") (pin "11") (pinfunction "11_11") (pintype "passive"))
    )
    (net (code "58") (name "unconnected-(JP2-Pad12)") (class "Default")
      (node (ref "JP2") (pin "12") (pinfunction "12_12") (pintype "passive"))
    )
    (net (code "59") (name "unconnected-(JP2-Pad13)") (class "Default")
      (node (ref "JP2") (pin "13") (pinfunction "13_13") (pintype "passive"))
    )
    (net (code "60") (name "unconnected-(JP2-Pad14)") (class "Default")
      (node (ref "JP2") (pin "14") (pinfunction "14_14") (pintype "passive"))
    )
    (net (code "61") (name "unconnected-(JP2-Pad15)") (class "Default")
      (node (ref "JP2") (pin "15") (pinfunction "15_15") (pintype "passive"))
    )
    (net (code "62") (name "unconnected-(JP2-Pad16)") (class "Default")
      (node (ref "JP2") (pin "16") (pinfunction "16_16") (pintype "passive"))
    )
    (net (code "63") (name "unconnected-(U2-NC{slash}FB-Pad4)") (class "Default")
      (node (ref "U2") (pin "4") (pinfunction "NC/FB_4") (pintype "passive"))
    )
    (net (code "64") (name "unconnected-(U4-NC-Pad1)") (class "Default")
      (node (ref "U4") (pin "1") (pinfunction "NC_1") (pintype "no_connect"))
    )
    (net (code "65") (name "unconnected-(U7-2A-Pad5)") (class "Default")
      (node (ref "U7") (pin "5") (pinfunction "2A_5") (pintype "input"))
    )
    (net (code "66") (name "unconnected-(U7-2Y-Pad4)") (class "Default")
      (node (ref "U7") (pin "4") (pinfunction "2Y_4") (pintype "output"))
    )
    (net (code "67") (name "unconnected-(U7-5A-Pad11)") (class "Default")
      (node (ref "U7") (pin "11") (pinfunction "5A_11") (pintype "input"))
    )
    (net (code "68") (name "unconnected-(U7-5Y-Pad12)") (class "Default")
      (node (ref "U7") (pin "12") (pinfunction "5Y_12") (pintype "output"))
    )
    (net (code "69") (name "unconnected-(U7-NC-Pad16)") (class "Default")
      (node (ref "U7") (pin "16") (pinfunction "NC_16") (pintype "no_connect"))
    )
    (net (code "70") (name "unconnected-(U7-NC_2-Pad13)") (class "Default")
      (node (ref "U7") (pin "13") (pinfunction "NC_2_13") (pintype "no_connect"))
    )
    (net (code "71") (name "unconnected-(U8-NC-Pad1)") (class "Default")
      (node (ref "U8") (pin "1") (pinfunction "NC_1") (pintype "bidirectional"))
    )
    (net (code "72") (name "unconnected-(U8-RSV-Pad8)") (class "Default")
      (node (ref "U8") (pin "8") (pinfunction "RSV_8") (pintype "bidirectional"))
    )
    (net (code "73") (name "unconnected-(U8-SHIELD-PadCD1)") (class "Default")
      (node (ref "U8") (pin "CD1") (pinfunction "SHIELD_CD1") (pintype "bidirectional"))
    )
    (net (code "74") (name "unconnected-(U8-SHIELD-PadCD2)") (class "Default")
      (node (ref "U8") (pin "CD2") (pinfunction "SHIELD_CD2") (pintype "bidirectional"))
    )
    (net (code "75") (name "unconnected-(U9-32KHZ-Pad3)") (class "Default")
      (node (ref "U9") (pin "3") (pinfunction "32KHZ_3") (pintype "bidirectional"))
    )
    (net (code "76") (name "unconnected-(U9-RST-Pad6)") (class "Default")
      (node (ref "U9") (pin "6") (pinfunction "RST_6") (pintype "bidirectional"))
    )
    (net (code "77") (name "unconnected-(U10-NC-Pad1)") (class "Default")
      (node (ref "U10") (pin "1") (pinfunction "NC_1") (pintype "no_connect"))
    )
  )
)
